# TMC2209_Camera_Slider_PCB_revB.net
KiCad netlist of a schematic drawn in EAGLE
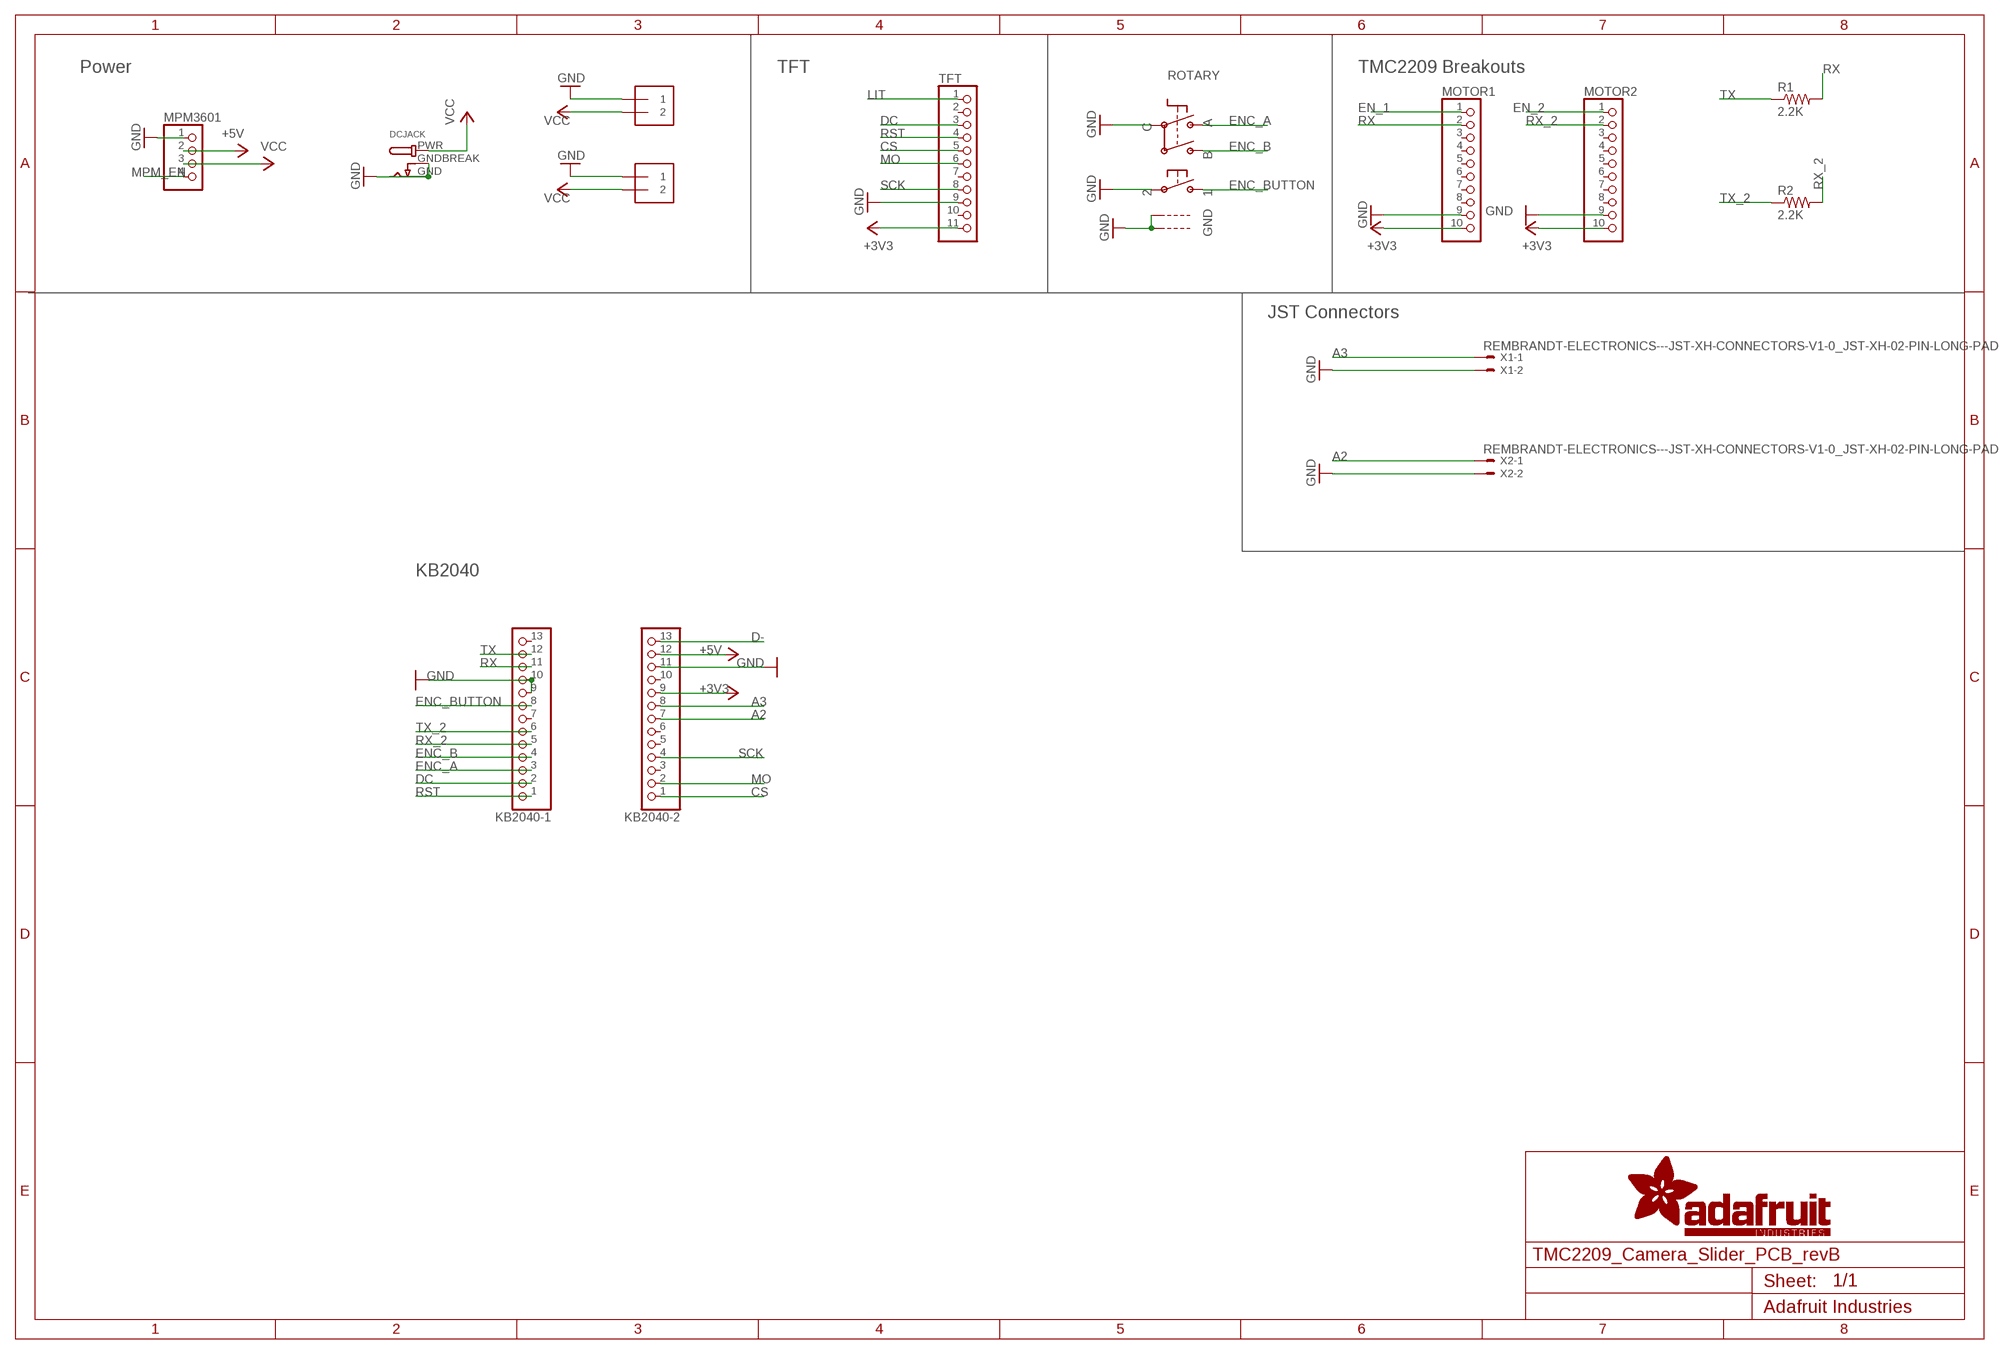
[diagram p0: schematic, sheet 1]

(export (version "E")
  (design (tool "Eeschema 10.0.6"))
  (components
    (comp (ref "DCJACK")
      (value "DCBARRELPTH")
      (footprint "eagle-import:DCJACK_2MM_PTH")
      (libsource (lib "eagle-import") (part "DCBARRELPTH"))
    )
    (comp (ref "J1")
      (value "1X2-3.5MM")
      (footprint "eagle-import:1X2-3.5MM")
      (libsource (lib "eagle-import") (part "1X2-3.5MM"))
    )
    (comp (ref "J2")
      (value "1X2-3.5MM")
      (footprint "eagle-import:1X2-3.5MM")
      (libsource (lib "eagle-import") (part "1X2-3.5MM"))
    )
    (comp (ref "KB2040-1")
      (value "HEADER-1X13")
      (footprint "eagle-import:1X13_ROUND_70")
      (libsource (lib "eagle-import") (part "HEADER-1X13"))
    )
    (comp (ref "KB2040-2")
      (value "HEADER-1X13")
      (footprint "eagle-import:1X13_ROUND_70")
      (libsource (lib "eagle-import") (part "HEADER-1X13"))
    )
    (comp (ref "MOTOR1")
      (value "HEADER-1X10")
      (footprint "eagle-import:1X10_OVAL")
      (libsource (lib "eagle-import") (part "HEADER-1X10"))
    )
    (comp (ref "MOTOR2")
      (value "HEADER-1X10")
      (footprint "eagle-import:1X10_OVAL")
      (libsource (lib "eagle-import") (part "HEADER-1X10"))
    )
    (comp (ref "MPM3601")
      (value "HEADER-1X4")
      (footprint "eagle-import:1X04_OVAL")
      (libsource (lib "eagle-import") (part "HEADER-1X4"))
    )
    (comp (ref "R1")
      (value "2.2K")
      (footprint "eagle-import:0309_12")
      (libsource (lib "eagle-import") (part "R-US_0309/12"))
    )
    (comp (ref "R2")
      (value "2.2K")
      (footprint "eagle-import:0309_12")
      (libsource (lib "eagle-import") (part "R-US_0309/12"))
    )
    (comp (ref "ROTARY")
      (value "ENCODER_PLUS_SWITCH_BOURNS_PEC11")
      (footprint "eagle-import:PEC11+SWITCH")
      (libsource (lib "eagle-import") (part "ENCODER_PLUS_SWITCH_PEC11_BOURNS"))
    )
    (comp (ref "TFT")
      (value "HEADER-1X11")
      (footprint "eagle-import:1X11_ROUND")
      (libsource (lib "eagle-import") (part "HEADER-1X11"))
    )
    (comp (ref "X1")
      (value "REMBRANDT-ELECTRONICS---JST-XH-CONNECTORS-V1-0_JST-XH-02-PIN-LONG-PAD")
      (footprint "eagle-import:REMBRANDT-ELECTRONICS---JST-XH-CONNECTORS-V1-0_JST-XH-02-PACKAGE-LONG-PAD")
      (libsource (lib "eagle-import") (part "REMBRANDT-ELECTRONICS---JST-XH-CONNECTORS-V1-0_JST-XH-02-PIN-LONG-PAD"))
    )
    (comp (ref "X2")
      (value "REMBRANDT-ELECTRONICS---JST-XH-CONNECTORS-V1-0_JST-XH-02-PIN-LONG-PAD")
      (footprint "eagle-import:REMBRANDT-ELECTRONICS---JST-XH-CONNECTORS-V1-0_JST-XH-02-PACKAGE-LONG-PAD")
      (libsource (lib "eagle-import") (part "REMBRANDT-ELECTRONICS---JST-XH-CONNECTORS-V1-0_JST-XH-02-PIN-LONG-PAD"))
    )
  )
  (nets
    (net (code "1") (name "+3V3") (class "Default")
      (node (ref "KB2040-2") (pin "9") (pinfunction "9_9") (pintype "passive"))
      (node (ref "MOTOR1") (pin "10") (pinfunction "10_10") (pintype "passive"))
      (node (ref "MOTOR2") (pin "10") (pinfunction "10_10") (pintype "passive"))
      (node (ref "TFT") (pin "11") (pinfunction "11_11") (pintype "passive"))
    )
    (net (code "2") (name "+5V") (class "Default")
      (node (ref "KB2040-2") (pin "12") (pinfunction "12_12") (pintype "passive"))
      (node (ref "MPM3601") (pin "2") (pinfunction "2_2") (pintype "passive"))
    )
    (net (code "3") (name "/A2") (class "Default")
      (node (ref "KB2040-2") (pin "7") (pinfunction "7_7") (pintype "passive"))
      (node (ref "X2") (pin "1") (pinfunction "S_1") (pintype "passive"))
    )
    (net (code "4") (name "/A3") (class "Default")
      (node (ref "KB2040-2") (pin "8") (pinfunction "8_8") (pintype "passive"))
      (node (ref "X1") (pin "1") (pinfunction "S_1") (pintype "passive"))
    )
    (net (code "5") (name "/CS") (class "Default")
      (node (ref "KB2040-2") (pin "1") (pinfunction "1_1") (pintype "passive"))
      (node (ref "TFT") (pin "5") (pinfunction "5_5") (pintype "passive"))
    )
    (net (code "6") (name "/D-") (class "Default")
      (node (ref "KB2040-2") (pin "13") (pinfunction "13_13") (pintype "passive"))
    )
    (net (code "7") (name "/DC") (class "Default")
      (node (ref "KB2040-1") (pin "2") (pinfunction "2_2") (pintype "passive"))
      (node (ref "TFT") (pin "3") (pinfunction "3_3") (pintype "passive"))
    )
    (net (code "8") (name "/ENC_A") (class "Default")
      (node (ref "KB2040-1") (pin "3") (pinfunction "3_3") (pintype "passive"))
      (node (ref "ROTARY") (pin "P$A") (pinfunction "P$A_P$A") (pintype "passive"))
    )
    (net (code "9") (name "/ENC_B") (class "Default")
      (node (ref "KB2040-1") (pin "4") (pinfunction "4_4") (pintype "passive"))
      (node (ref "ROTARY") (pin "P$B") (pinfunction "P$B_P$B") (pintype "passive"))
    )
    (net (code "10") (name "/ENC_BUTTON") (class "Default")
      (node (ref "KB2040-1") (pin "8") (pinfunction "8_8") (pintype "passive"))
      (node (ref "ROTARY") (pin "P$1") (pinfunction "P$1_P$1") (pintype "passive"))
    )
    (net (code "11") (name "/EN_1") (class "Default")
      (node (ref "MOTOR1") (pin "1") (pinfunction "1_1") (pintype "passive"))
    )
    (net (code "12") (name "/EN_2") (class "Default")
      (node (ref "MOTOR2") (pin "1") (pinfunction "1_1") (pintype "passive"))
    )
    (net (code "13") (name "/LIT") (class "Default")
      (node (ref "TFT") (pin "1") (pinfunction "1_1") (pintype "passive"))
    )
    (net (code "14") (name "/MO") (class "Default")
      (node (ref "KB2040-2") (pin "2") (pinfunction "2_2") (pintype "passive"))
      (node (ref "TFT") (pin "6") (pinfunction "6_6") (pintype "passive"))
    )
    (net (code "15") (name "/MPM_EN") (class "Default")
      (node (ref "MPM3601") (pin "4") (pinfunction "4_4") (pintype "passive"))
    )
    (net (code "16") (name "/RST") (class "Default")
      (node (ref "KB2040-1") (pin "1") (pinfunction "1_1") (pintype "passive"))
      (node (ref "TFT") (pin "4") (pinfunction "4_4") (pintype "passive"))
    )
    (net (code "17") (name "/RX") (class "Default")
      (node (ref "KB2040-1") (pin "11") (pinfunction "11_11") (pintype "passive"))
      (node (ref "MOTOR1") (pin "2") (pinfunction "2_2") (pintype "passive"))
      (node (ref "R1") (pin "2") (pinfunction "2_2") (pintype "passive"))
    )
    (net (code "18") (name "/RX_2") (class "Default")
      (node (ref "KB2040-1") (pin "5") (pinfunction "5_5") (pintype "passive"))
      (node (ref "MOTOR2") (pin "2") (pinfunction "2_2") (pintype "passive"))
      (node (ref "R2") (pin "2") (pinfunction "2_2") (pintype "passive"))
    )
    (net (code "19") (name "/SCK") (class "Default")
      (node (ref "KB2040-2") (pin "4") (pinfunction "4_4") (pintype "passive"))
      (node (ref "TFT") (pin "8") (pinfunction "8_8") (pintype "passive"))
    )
    (net (code "20") (name "/TX") (class "Default")
      (node (ref "KB2040-1") (pin "12") (pinfunction "12_12") (pintype "passive"))
      (node (ref "R1") (pin "1") (pinfunction "1_1") (pintype "passive"))
    )
    (net (code "21") (name "/TX_2") (class "Default")
      (node (ref "KB2040-1") (pin "6") (pinfunction "6_6") (pintype "passive"))
      (node (ref "R2") (pin "1") (pinfunction "1_1") (pintype "passive"))
    )
    (net (code "22") (name "GND") (class "Default")
      (node (ref "DCJACK") (pin "GND") (pinfunction "GND_GND") (pintype "power_in"))
      (node (ref "DCJACK") (pin "GNDBREAK") (pinfunction "GNDBREAK_GNDBREAK") (pintype "power_in"))
      (node (ref "J1") (pin "1") (pinfunction "1_1") (pintype "passive"))
      (node (ref "J2") (pin "1") (pinfunction "1_1") (pintype "passive"))
      (node (ref "KB2040-1") (pin "10") (pinfunction "10_10") (pintype "passive"))
      (node (ref "KB2040-1") (pin "9") (pinfunction "9_9") (pintype "passive"))
      (node (ref "KB2040-2") (pin "11") (pinfunction "11_11") (pintype "passive"))
      (node (ref "MOTOR1") (pin "9") (pinfunction "9_9") (pintype "passive"))
      (node (ref "MOTOR2") (pin "9") (pinfunction "9_9") (pintype "passive"))
      (node (ref "MPM3601") (pin "1") (pinfunction "1_1") (pintype "passive"))
      (node (ref "ROTARY") (pin "P$2") (pinfunction "P$2_P$2") (pintype "passive"))
      (node (ref "ROTARY") (pin "P$C") (pinfunction "P$C_P$C") (pintype "passive"))
      (node (ref "ROTARY") (pin "P$GND1") (pinfunction "P$GND1_P$GND1") (pintype "passive"))
      (node (ref "ROTARY") (pin "P$GND2") (pinfunction "P$GND2_P$GND2") (pintype "passive"))
      (node (ref "TFT") (pin "9") (pinfunction "9_9") (pintype "passive"))
      (node (ref "X1") (pin "2") (pinfunction "S_2") (pintype "passive"))
      (node (ref "X2") (pin "2") (pinfunction "S_2") (pintype "passive"))
    )
    (net (code "23") (name "VCC") (class "Default")
      (node (ref "DCJACK") (pin "PWR") (pinfunction "PWR_PWR") (pintype "power_in"))
      (node (ref "J1") (pin "2") (pinfunction "2_2") (pintype "passive"))
      (node (ref "J2") (pin "2") (pinfunction "2_2") (pintype "passive"))
      (node (ref "MPM3601") (pin "3") (pinfunction "3_3") (pintype "passive"))
    )
    (net (code "24") (name "unconnected-(KB2040-1-Pad7)") (class "Default")
      (node (ref "KB2040-1") (pin "7") (pinfunction "7_7") (pintype "passive"))
    )
    (net (code "25") (name "unconnected-(KB2040-1-Pad13)") (class "Default")
      (node (ref "KB2040-1") (pin "13") (pinfunction "13_13") (pintype "passive"))
    )
    (net (code "26") (name "unconnected-(KB2040-2-Pad3)") (class "Default")
      (node (ref "KB2040-2") (pin "3") (pinfunction "3_3") (pintype "passive"))
    )
    (net (code "27") (name "unconnected-(KB2040-2-Pad5)") (class "Default")
      (node (ref "KB2040-2") (pin "5") (pinfunction "5_5") (pintype "passive"))
    )
    (net (code "28") (name "unconnected-(KB2040-2-Pad6)") (class "Default")
      (node (ref "KB2040-2") (pin "6") (pinfunction "6_6") (pintype "passive"))
    )
    (net (code "29") (name "unconnected-(KB2040-2-Pad10)") (class "Default")
      (node (ref "KB2040-2") (pin "10") (pinfunction "10_10") (pintype "passive"))
    )
    (net (code "30") (name "unconnected-(MOTOR1-Pad3)") (class "Default")
      (node (ref "MOTOR1") (pin "3") (pinfunction "3_3") (pintype "passive"))
    )
    (net (code "31") (name "unconnected-(MOTOR1-Pad4)") (class "Default")
      (node (ref "MOTOR1") (pin "4") (pinfunction "4_4") (pintype "passive"))
    )
    (net (code "32") (name "unconnected-(MOTOR1-Pad5)") (class "Default")
      (node (ref "MOTOR1") (pin "5") (pinfunction "5_5") (pintype "passive"))
    )
    (net (code "33") (name "unconnected-(MOTOR1-Pad6)") (class "Default")
      (node (ref "MOTOR1") (pin "6") (pinfunction "6_6") (pintype "passive"))
    )
    (net (code "34") (name "unconnected-(MOTOR1-Pad7)") (class "Default")
      (node (ref "MOTOR1") (pin "7") (pinfunction "7_7") (pintype "passive"))
    )
    (net (code "35") (name "unconnected-(MOTOR1-Pad8)") (class "Default")
      (node (ref "MOTOR1") (pin "8") (pinfunction "8_8") (pintype "passive"))
    )
    (net (code "36") (name "unconnected-(MOTOR2-Pad3)") (class "Default")
      (node (ref "MOTOR2") (pin "3") (pinfunction "3_3") (pintype "passive"))
    )
    (net (code "37") (name "unconnected-(MOTOR2-Pad4)") (class "Default")
      (node (ref "MOTOR2") (pin "4") (pinfunction "4_4") (pintype "passive"))
    )
    (net (code "38") (name "unconnected-(MOTOR2-Pad5)") (class "Default")
      (node (ref "MOTOR2") (pin "5") (pinfunction "5_5") (pintype "passive"))
    )
    (net (code "39") (name "unconnected-(MOTOR2-Pad6)") (class "Default")
      (node (ref "MOTOR2") (pin "6") (pinfunction "6_6") (pintype "passive"))
    )
    (net (code "40") (name "unconnected-(MOTOR2-Pad7)") (class "Default")
      (node (ref "MOTOR2") (pin "7") (pinfunction "7_7") (pintype "passive"))
    )
    (net (code "41") (name "unconnected-(MOTOR2-Pad8)") (class "Default")
      (node (ref "MOTOR2") (pin "8") (pinfunction "8_8") (pintype "passive"))
    )
    (net (code "42") (name "unconnected-(TFT-Pad2)") (class "Default")
      (node (ref "TFT") (pin "2") (pinfunction "2_2") (pintype "passive"))
    )
    (net (code "43") (name "unconnected-(TFT-Pad7)") (class "Default")
      (node (ref "TFT") (pin "7") (pinfunction "7_7") (pintype "passive"))
    )
    (net (code "44") (name "unconnected-(TFT-Pad10)") (class "Default")
      (node (ref "TFT") (pin "10") (pinfunction "10_10") (pintype "passive"))
    )
  )
)
